# power_node.net
KiCad netlist of a schematic drawn in EAGLE
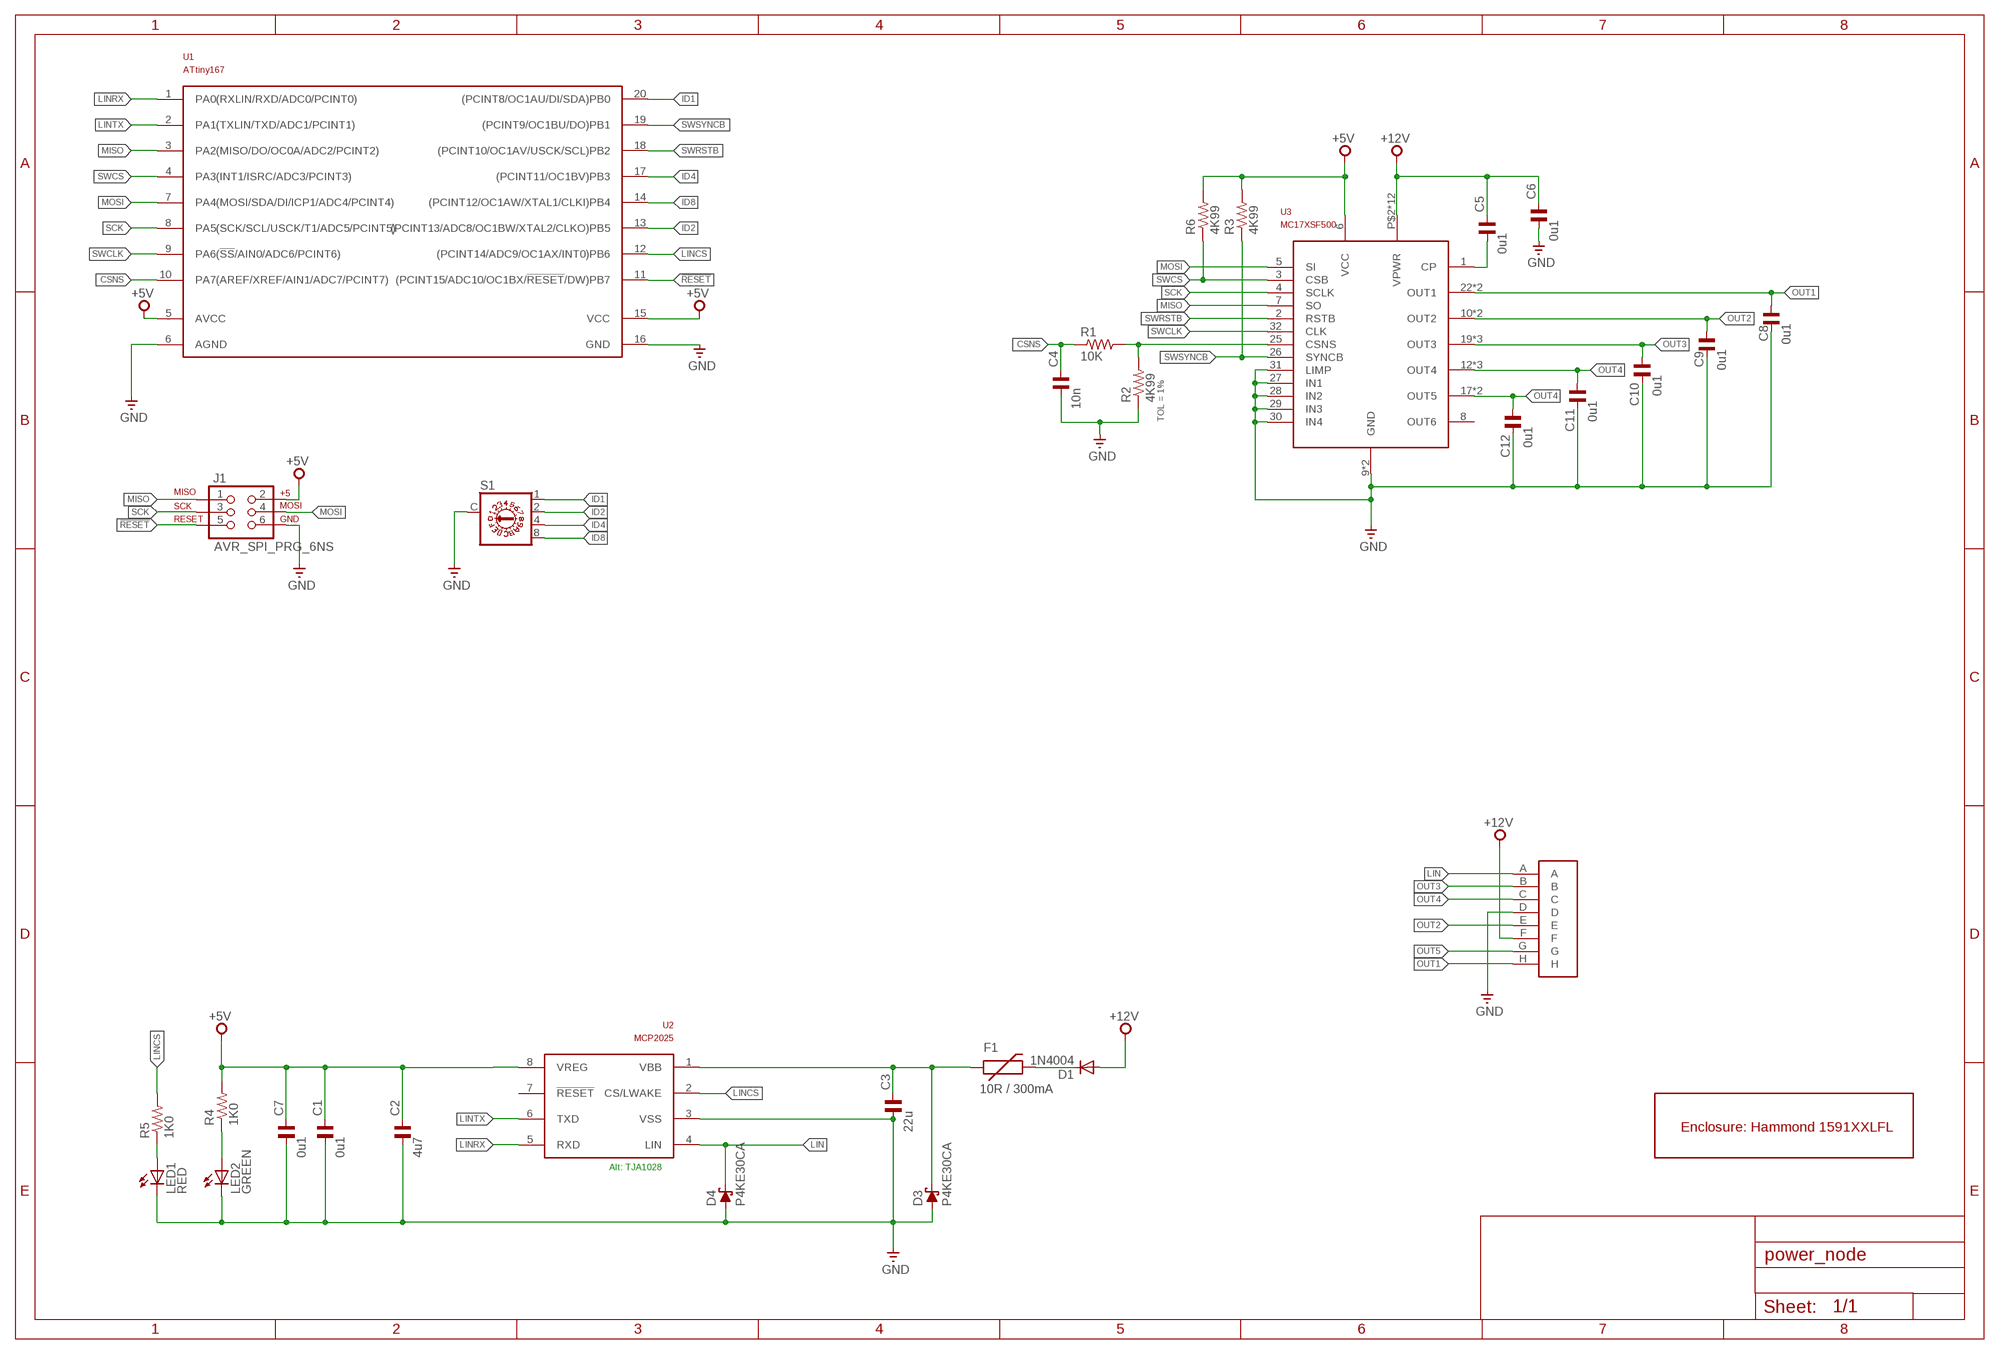
[diagram p0: schematic, sheet 1]

(export (version "E")
  (design (tool "Eeschema 10.0.6"))
  (components
    (comp (ref "C1")
      (value "0u1")
      (footprint "eagle-import:C050-024X044")
      (fields (field (name "PARTNO") "FK28X7R1H104K"))
      (libsource (lib "eagle-import") (part "C-EU050-024X044"))
    )
    (comp (ref "C2")
      (value "4u7")
      (footprint "eagle-import:C050-024X044")
      (fields (field (name "PARTNO") "FK28X5R0J475K"))
      (libsource (lib "eagle-import") (part "C-EU050-024X044"))
    )
    (comp (ref "C3")
      (value "22u")
      (footprint "eagle-import:C050-024X044")
      (fields (field (name "PARTNO") "FK22X5R1E226M"))
      (libsource (lib "eagle-import") (part "C-EU050-024X044"))
    )
    (comp (ref "C4")
      (value "10n")
      (footprint "eagle-import:C025-024X044")
      (fields (field (name "PARTNO") "FK18X7R1H103K"))
      (libsource (lib "eagle-import") (part "C-EU025-024X044"))
    )
    (comp (ref "C5")
      (value "0u1")
      (footprint "eagle-import:C050-024X044")
      (fields (field (name "PARTNO") "FK28X7R1H104K"))
      (libsource (lib "eagle-import") (part "C-EU050-024X044"))
    )
    (comp (ref "C6")
      (value "0u1")
      (footprint "eagle-import:C050-024X044")
      (fields (field (name "PARTNO") "FK28X7R1H104K"))
      (libsource (lib "eagle-import") (part "C-EU050-024X044"))
    )
    (comp (ref "C7")
      (value "0u1")
      (footprint "eagle-import:C050-024X044")
      (fields (field (name "PARTNO") "FK28X7R1H104K"))
      (libsource (lib "eagle-import") (part "C-EU050-024X044"))
    )
    (comp (ref "C8")
      (value "0u1")
      (footprint "eagle-import:C0603K")
      (fields (field (name "PARTNO") "C1608X7R1H104M080AA"))
      (libsource (lib "eagle-import") (part "C-EUC0603K"))
    )
    (comp (ref "C9")
      (value "0u1")
      (footprint "eagle-import:C0603K")
      (fields (field (name "PARTNO") "C1608X7R1H104M080AA"))
      (libsource (lib "eagle-import") (part "C-EUC0603K"))
    )
    (comp (ref "C10")
      (value "0u1")
      (footprint "eagle-import:C0603K")
      (fields (field (name "PARTNO") "C1608X7R1H104M080AA"))
      (libsource (lib "eagle-import") (part "C-EUC0603K"))
    )
    (comp (ref "C11")
      (value "0u1")
      (footprint "eagle-import:C0603K")
      (fields (field (name "PARTNO") "C1608X7R1H104M080AA"))
      (libsource (lib "eagle-import") (part "C-EUC0603K"))
    )
    (comp (ref "C12")
      (value "0u1")
      (footprint "eagle-import:C0603K")
      (fields (field (name "PARTNO") "C1608X7R1H104M080AA"))
      (libsource (lib "eagle-import") (part "C-EUC0603K"))
    )
    (comp (ref "D1")
      (value "1N4004")
      (footprint "eagle-import:DO41-10")
      (fields (field (name "PARTNO") "1N4004-TP"))
      (libsource (lib "eagle-import") (part "1N4004"))
    )
    (comp (ref "D3")
      (value "P4KE30CA")
      (footprint "eagle-import:DO41-10")
      (libsource (lib "eagle-import") (part "P4KEXX"))
    )
    (comp (ref "D4")
      (value "P4KE30CA")
      (footprint "eagle-import:DO41-10")
      (libsource (lib "eagle-import") (part "P4KEXX"))
    )
    (comp (ref "F1")
      (value "10R / 300mA")
      (footprint "eagle-import:PTC")
      (fields (field (name "PARTNO") "CMF-RL10-0"))
      (libsource (lib "eagle-import") (part "PTCPTH"))
    )
    (comp (ref "J1")
      (value "AVR_SPI_PRG_6NS")
      (footprint "eagle-import:2X3-NS")
      (libsource (lib "eagle-import") (part "AVR_SPI_PRG_6NS"))
    )
    (comp (ref "J2")
      (value "12146734")
      (footprint "eagle-import:12146734")
      (fields (field (name "PARTNO") "12146724-B"))
      (libsource (lib "eagle-import") (part "12146734"))
    )
    (comp (ref "LED1")
      (value "RED")
      (footprint "eagle-import:LED3MM")
      (fields (field (name "PARTNO") "C4SMF-RJS-CT0W0BB2"))
      (libsource (lib "eagle-import") (part "LED3MM"))
    )
    (comp (ref "LED2")
      (value "GREEN")
      (footprint "eagle-import:LED3MM")
      (fields (field (name "PARTNO") "C4SMF-GJS-CV0Y0792"))
      (libsource (lib "eagle-import") (part "LED3MM"))
    )
    (comp (ref "R1")
      (value "10K")
      (footprint "eagle-import:0207_10")
      (fields (field (name "PARTNO") "CF14JT10K0"))
      (libsource (lib "eagle-import") (part "R-EU_0207/10"))
    )
    (comp (ref "R2")
      (value "4K99")
      (footprint "eagle-import:0207_10")
      (fields (field (name "PARTNO") "MFR-25FBF52-4K99") (field (name "TOL") "1%"))
      (libsource (lib "eagle-import") (part "R-EU_0207/10"))
    )
    (comp (ref "R3")
      (value "4K99")
      (footprint "eagle-import:0207_10")
      (fields (field (name "PARTNO") "MFR-25FBF52-4K99"))
      (libsource (lib "eagle-import") (part "R-EU_0207/10"))
    )
    (comp (ref "R4")
      (value "1K0")
      (footprint "eagle-import:0207_10")
      (fields (field (name "PARTNO") "CF14JT1K00"))
      (libsource (lib "eagle-import") (part "R-EU_0207/10"))
    )
    (comp (ref "R5")
      (value "1K0")
      (footprint "eagle-import:0207_10")
      (fields (field (name "PARTNO") "CF14JT1K00"))
      (libsource (lib "eagle-import") (part "R-EU_0207/10"))
    )
    (comp (ref "R6")
      (value "4K99")
      (footprint "eagle-import:0207_10")
      (fields (field (name "PARTNO") "MFR-25FBF52-4K99"))
      (libsource (lib "eagle-import") (part "R-EU_0207/10"))
    )
    (comp (ref "S1")
      (value "P103")
      (footprint "eagle-import:P103")
      (fields (field (name "PARTNO") "SH-7050MC"))
      (libsource (lib "eagle-import") (part "P103"))
    )
    (comp (ref "U$1")
      (value "1591XXLFL")
      (footprint "eagle-import:1591XXLFL")
      (fields (field (name "PARTNO") "1591XXLFLBK"))
      (libsource (lib "eagle-import") (part "1591XXLFL"))
    )
    (comp (ref "U1")
      (value "ATtiny167")
      (footprint "eagle-import:SO20W")
      (fields (field (name "PARTNO") "ATTINY167-SU"))
      (libsource (lib "eagle-import") (part "ATTINY167"))
    )
    (comp (ref "U2")
      (value "MCP2025")
      (footprint "eagle-import:SO08")
      (fields (field (name "PARTNO") "MCP2025-500E/SN"))
      (libsource (lib "eagle-import") (part "MCP2025"))
    )
    (comp (ref "U3")
      (value "MC17XSF500")
      (footprint "eagle-import:SOIC32W-EP")
      (fields (field (name "PARTNO") "MC17XSF500EK"))
      (libsource (lib "eagle-import") (part "MC17XSF500"))
    )
  )
  (nets
    (net (code "1") (name "+5V") (class "Default")
      (node (ref "C1") (pin "1") (pinfunction "1_1") (pintype "passive"))
      (node (ref "C2") (pin "1") (pinfunction "1_1") (pintype "passive"))
      (node (ref "C7") (pin "1") (pinfunction "1_1") (pintype "passive"))
      (node (ref "J1") (pin "2") (pinfunction "2_2") (pintype "passive"))
      (node (ref "R3") (pin "2") (pinfunction "2_2") (pintype "passive"))
      (node (ref "R4") (pin "2") (pinfunction "2_2") (pintype "passive"))
      (node (ref "R6") (pin "2") (pinfunction "2_2") (pintype "passive"))
      (node (ref "U1") (pin "15") (pinfunction "VCC_15") (pintype "power_in"))
      (node (ref "U1") (pin "5") (pinfunction "AVCC_5") (pintype "power_in"))
      (node (ref "U2") (pin "8") (pinfunction "VREG_8") (pintype "power_in"))
      (node (ref "U3") (pin "6") (pinfunction "VCC_6") (pintype "power_in"))
    )
    (net (code "2") (name "+12V") (class "Default")
      (node (ref "C5") (pin "1") (pinfunction "1_1") (pintype "passive"))
      (node (ref "C6") (pin "1") (pinfunction "1_1") (pintype "passive"))
      (node (ref "D1") (pin "A") (pinfunction "A_A") (pintype "passive"))
      (node (ref "J2") (pin "F") (pinfunction "F_F") (pintype "bidirectional"))
      (node (ref "U3") (pin "P$10") (pinfunction "VPWR_P$10") (pintype "power_in"))
      (node (ref "U3") (pin "P$11") (pinfunction "VPWR_P$11") (pintype "power_in"))
      (node (ref "U3") (pin "P$12") (pinfunction "VPWR_P$12") (pintype "power_in"))
      (node (ref "U3") (pin "P$13") (pinfunction "VPWR_P$13") (pintype "power_in"))
      (node (ref "U3") (pin "P$2") (pinfunction "VPWR_P$2") (pintype "power_in"))
      (node (ref "U3") (pin "P$3") (pinfunction "VPWR_P$3") (pintype "power_in"))
      (node (ref "U3") (pin "P$4") (pinfunction "VPWR_P$4") (pintype "power_in"))
      (node (ref "U3") (pin "P$5") (pinfunction "VPWR_P$5") (pintype "power_in"))
      (node (ref "U3") (pin "P$6") (pinfunction "VPWR_P$6") (pintype "power_in"))
      (node (ref "U3") (pin "P$7") (pinfunction "VPWR_P$7") (pintype "power_in"))
      (node (ref "U3") (pin "P$8") (pinfunction "VPWR_P$8") (pintype "power_in"))
      (node (ref "U3") (pin "P$9") (pinfunction "VPWR_P$9") (pintype "power_in"))
    )
    (net (code "3") (name "/~{RESET}") (class "Default")
      (node (ref "J1") (pin "5") (pinfunction "5_5") (pintype "passive"))
      (node (ref "U1") (pin "11") (pinfunction "(PCINT15/ADC10/OC1BX/~{RESET}/DW)PB7_11") (pintype "bidirectional"))
    )
    (net (code "4") (name "CSNS") (class "Default")
      (node (ref "C4") (pin "1") (pinfunction "1_1") (pintype "passive"))
      (node (ref "R1") (pin "1") (pinfunction "1_1") (pintype "passive"))
      (node (ref "U1") (pin "10") (pinfunction "PA7(AREF/XREF/AIN1/ADC7/PCINT7)_10") (pintype "bidirectional"))
    )
    (net (code "5") (name "GND") (class "Default")
      (node (ref "C1") (pin "2") (pinfunction "2_2") (pintype "passive"))
      (node (ref "C10") (pin "2") (pinfunction "2_2") (pintype "passive"))
      (node (ref "C11") (pin "2") (pinfunction "2_2") (pintype "passive"))
      (node (ref "C12") (pin "2") (pinfunction "2_2") (pintype "passive"))
      (node (ref "C2") (pin "2") (pinfunction "2_2") (pintype "passive"))
      (node (ref "C3") (pin "2") (pinfunction "2_2") (pintype "passive"))
      (node (ref "C4") (pin "2") (pinfunction "2_2") (pintype "passive"))
      (node (ref "C6") (pin "2") (pinfunction "2_2") (pintype "passive"))
      (node (ref "C7") (pin "2") (pinfunction "2_2") (pintype "passive"))
      (node (ref "C8") (pin "2") (pinfunction "2_2") (pintype "passive"))
      (node (ref "C9") (pin "2") (pinfunction "2_2") (pintype "passive"))
      (node (ref "D3") (pin "A") (pinfunction "A_A") (pintype "passive"))
      (node (ref "D4") (pin "A") (pinfunction "A_A") (pintype "passive"))
      (node (ref "J1") (pin "6") (pinfunction "6_6") (pintype "passive"))
      (node (ref "J2") (pin "D") (pinfunction "D_D") (pintype "bidirectional"))
      (node (ref "LED1") (pin "K") (pinfunction "C_K") (pintype "passive"))
      (node (ref "LED2") (pin "K") (pinfunction "C_K") (pintype "passive"))
      (node (ref "R2") (pin "1") (pinfunction "1_1") (pintype "passive"))
      (node (ref "S1") (pin "C") (pinfunction "C_C") (pintype "passive"))
      (node (ref "U1") (pin "16") (pinfunction "GND_16") (pintype "power_in"))
      (node (ref "U1") (pin "6") (pinfunction "AGND_6") (pintype "power_in"))
      (node (ref "U2") (pin "3") (pinfunction "VSS_3") (pintype "power_in"))
      (node (ref "U3") (pin "24") (pinfunction "GND_24") (pintype "power_in"))
      (node (ref "U3") (pin "27") (pinfunction "IN1_27") (pintype "input"))
      (node (ref "U3") (pin "28") (pinfunction "IN2_28") (pintype "input"))
      (node (ref "U3") (pin "29") (pinfunction "IN3_29") (pintype "input"))
      (node (ref "U3") (pin "30") (pinfunction "IN4_30") (pintype "input"))
      (node (ref "U3") (pin "31") (pinfunction "LIMP_31") (pintype "input"))
      (node (ref "U3") (pin "9") (pinfunction "GND_9") (pintype "power_in"))
    )
    (net (code "6") (name "ID1") (class "Default")
      (node (ref "S1") (pin "1") (pinfunction "1_1") (pintype "passive"))
      (node (ref "U1") (pin "20") (pinfunction "(PCINT8/OC1AU/DI/SDA)PB0_20") (pintype "bidirectional"))
    )
    (net (code "7") (name "ID2") (class "Default")
      (node (ref "S1") (pin "2") (pinfunction "2_2") (pintype "passive"))
      (node (ref "U1") (pin "13") (pinfunction "(PCINT13/ADC8/OC1BW/XTAL2/CLKO)PB5_13") (pintype "bidirectional"))
    )
    (net (code "8") (name "ID4") (class "Default")
      (node (ref "S1") (pin "4") (pinfunction "4_4") (pintype "passive"))
      (node (ref "U1") (pin "17") (pinfunction "(PCINT11/OC1BV)PB3_17") (pintype "bidirectional"))
    )
    (net (code "9") (name "ID8") (class "Default")
      (node (ref "S1") (pin "8") (pinfunction "8_8") (pintype "passive"))
      (node (ref "U1") (pin "14") (pinfunction "(PCINT12/OC1AW/XTAL1/CLKI)PB4_14") (pintype "bidirectional"))
    )
    (net (code "10") (name "LIN") (class "Default")
      (node (ref "D4") (pin "C") (pinfunction "C_C") (pintype "passive"))
      (node (ref "J2") (pin "A") (pinfunction "A_A") (pintype "bidirectional"))
      (node (ref "U2") (pin "4") (pinfunction "LIN_4") (pintype "bidirectional"))
    )
    (net (code "11") (name "LINCS") (class "Default")
      (node (ref "R5") (pin "2") (pinfunction "2_2") (pintype "passive"))
      (node (ref "U1") (pin "12") (pinfunction "(PCINT14/ADC9/OC1AX/INT0)PB6_12") (pintype "bidirectional"))
      (node (ref "U2") (pin "2") (pinfunction "CS/LWAKE_2") (pintype "input"))
    )
    (net (code "12") (name "LINRX") (class "Default")
      (node (ref "U1") (pin "1") (pinfunction "PA0(RXLIN/RXD/ADC0/PCINT0)_1") (pintype "bidirectional"))
      (node (ref "U2") (pin "5") (pinfunction "RXD_5") (pintype "output"))
    )
    (net (code "13") (name "LINTX") (class "Default")
      (node (ref "U1") (pin "2") (pinfunction "PA1(TXLIN/TXD/ADC1/PCINT1)_2") (pintype "bidirectional"))
      (node (ref "U2") (pin "6") (pinfunction "TXD_6") (pintype "input"))
    )
    (net (code "14") (name "MISO") (class "Default")
      (node (ref "J1") (pin "1") (pinfunction "1_1") (pintype "passive"))
      (node (ref "U1") (pin "3") (pinfunction "PA2(MISO/DO/OC0A/ADC2/PCINT2)_3") (pintype "bidirectional"))
      (node (ref "U3") (pin "7") (pinfunction "SO_7") (pintype "output"))
    )
    (net (code "15") (name "MOSI") (class "Default")
      (node (ref "J1") (pin "4") (pinfunction "4_4") (pintype "passive"))
      (node (ref "U1") (pin "7") (pinfunction "PA4(MOSI/SDA/DI/ICP1/ADC4/PCINT4)_7") (pintype "bidirectional"))
      (node (ref "U3") (pin "5") (pinfunction "SI_5") (pintype "input"))
    )
    (net (code "16") (name "Net-(F1-1)") (class "Default")
      (node (ref "C3") (pin "1") (pinfunction "1_1") (pintype "passive"))
      (node (ref "D3") (pin "C") (pinfunction "C_C") (pintype "passive"))
      (node (ref "F1") (pin "P$1") (pinfunction "1_P$1") (pintype "bidirectional"))
      (node (ref "U2") (pin "1") (pinfunction "VBB_1") (pintype "power_in"))
    )
    (net (code "17") (name "Net-(F1-2)") (class "Default")
      (node (ref "D1") (pin "C") (pinfunction "C_C") (pintype "passive"))
      (node (ref "F1") (pin "P$2") (pinfunction "2_P$2") (pintype "bidirectional"))
    )
    (net (code "18") (name "Net-(LED1-PadA)") (class "Default")
      (node (ref "LED1") (pin "A") (pinfunction "A_A") (pintype "passive"))
      (node (ref "R5") (pin "1") (pinfunction "1_1") (pintype "passive"))
    )
    (net (code "19") (name "Net-(LED2-PadA)") (class "Default")
      (node (ref "LED2") (pin "A") (pinfunction "A_A") (pintype "passive"))
      (node (ref "R4") (pin "1") (pinfunction "1_1") (pintype "passive"))
    )
    (net (code "20") (name "Net-(U3-CP)") (class "Default")
      (node (ref "C5") (pin "2") (pinfunction "2_2") (pintype "passive"))
      (node (ref "U3") (pin "1") (pinfunction "CP_1") (pintype "passive"))
    )
    (net (code "21") (name "Net-(U3-CSNS)") (class "Default")
      (node (ref "R1") (pin "2") (pinfunction "2_2") (pintype "passive"))
      (node (ref "R2") (pin "2") (pinfunction "2_2") (pintype "passive"))
      (node (ref "U3") (pin "25") (pinfunction "CSNS_25") (pintype "output"))
    )
    (net (code "22") (name "OUT1") (class "Default")
      (node (ref "C8") (pin "1") (pinfunction "1_1") (pintype "passive"))
      (node (ref "J2") (pin "H") (pinfunction "H_H") (pintype "bidirectional"))
      (node (ref "U3") (pin "22") (pinfunction "OUT1_22") (pintype "output"))
      (node (ref "U3") (pin "23") (pinfunction "OUT1_23") (pintype "output"))
    )
    (net (code "23") (name "OUT2") (class "Default")
      (node (ref "C9") (pin "1") (pinfunction "1_1") (pintype "passive"))
      (node (ref "J2") (pin "E") (pinfunction "E_E") (pintype "bidirectional"))
      (node (ref "U3") (pin "10") (pinfunction "OUT2_10") (pintype "output"))
      (node (ref "U3") (pin "11") (pinfunction "OUT2_11") (pintype "output"))
    )
    (net (code "24") (name "OUT3") (class "Default")
      (node (ref "C10") (pin "1") (pinfunction "1_1") (pintype "passive"))
      (node (ref "J2") (pin "B") (pinfunction "B_B") (pintype "bidirectional"))
      (node (ref "U3") (pin "19") (pinfunction "OUT3_19") (pintype "output"))
      (node (ref "U3") (pin "20") (pinfunction "OUT3_20") (pintype "output"))
      (node (ref "U3") (pin "21") (pinfunction "OUT3_21") (pintype "output"))
    )
    (net (code "25") (name "OUT4") (class "Default")
      (node (ref "C11") (pin "1") (pinfunction "1_1") (pintype "passive"))
      (node (ref "J2") (pin "C") (pinfunction "C_C") (pintype "bidirectional"))
      (node (ref "U3") (pin "12") (pinfunction "OUT4_12") (pintype "output"))
      (node (ref "U3") (pin "13") (pinfunction "OUT4_13") (pintype "output"))
      (node (ref "U3") (pin "14") (pinfunction "OUT4_14") (pintype "output"))
    )
    (net (code "26") (name "OUT5") (class "Default")
      (node (ref "C12") (pin "1") (pinfunction "1_1") (pintype "passive"))
      (node (ref "J2") (pin "G") (pinfunction "G_G") (pintype "bidirectional"))
      (node (ref "U3") (pin "17") (pinfunction "OUT5_17") (pintype "output"))
      (node (ref "U3") (pin "18") (pinfunction "OUT5_18") (pintype "output"))
    )
    (net (code "27") (name "SCK") (class "Default")
      (node (ref "J1") (pin "3") (pinfunction "3_3") (pintype "passive"))
      (node (ref "U1") (pin "8") (pinfunction "PA5(SCK/SCL/USCK/T1/ADC5/PCINT5)_8") (pintype "bidirectional"))
      (node (ref "U3") (pin "4") (pinfunction "SCLK_4") (pintype "input"))
    )
    (net (code "28") (name "SWCLK") (class "Default")
      (node (ref "U1") (pin "9") (pinfunction "PA6(~{SS}/AIN0/ADC6/PCINT6)_9") (pintype "bidirectional"))
      (node (ref "U3") (pin "32") (pinfunction "CLK_32") (pintype "bidirectional"))
    )
    (net (code "29") (name "SWCS") (class "Default")
      (node (ref "R6") (pin "1") (pinfunction "1_1") (pintype "passive"))
      (node (ref "U1") (pin "4") (pinfunction "PA3(INT1/ISRC/ADC3/PCINT3)_4") (pintype "bidirectional"))
      (node (ref "U3") (pin "3") (pinfunction "CSB_3") (pintype "input"))
    )
    (net (code "30") (name "SWRSTB") (class "Default")
      (node (ref "U1") (pin "18") (pinfunction "(PCINT10/OC1AV/USCK/SCL)PB2_18") (pintype "bidirectional"))
      (node (ref "U3") (pin "2") (pinfunction "RSTB_2") (pintype "input"))
    )
    (net (code "31") (name "SWSYNCB") (class "Default")
      (node (ref "R3") (pin "1") (pinfunction "1_1") (pintype "passive"))
      (node (ref "U1") (pin "19") (pinfunction "(PCINT9/OC1BU/DO)PB1_19") (pintype "bidirectional"))
      (node (ref "U3") (pin "26") (pinfunction "SYNCB_26") (pintype "open_collector"))
    )
    (net (code "32") (name "unconnected-(U2-~{RESET}-Pad7)") (class "Default")
      (node (ref "U2") (pin "7") (pinfunction "~{RESET}_7") (pintype "open_collector"))
    )
    (net (code "33") (name "unconnected-(U3-OUT6-Pad8)") (class "Default")
      (node (ref "U3") (pin "8") (pinfunction "OUT6_8") (pintype "output"))
    )
  )
)
